# ledSequencer.net
KiCad netlist of a schematic drawn in Altium Designer
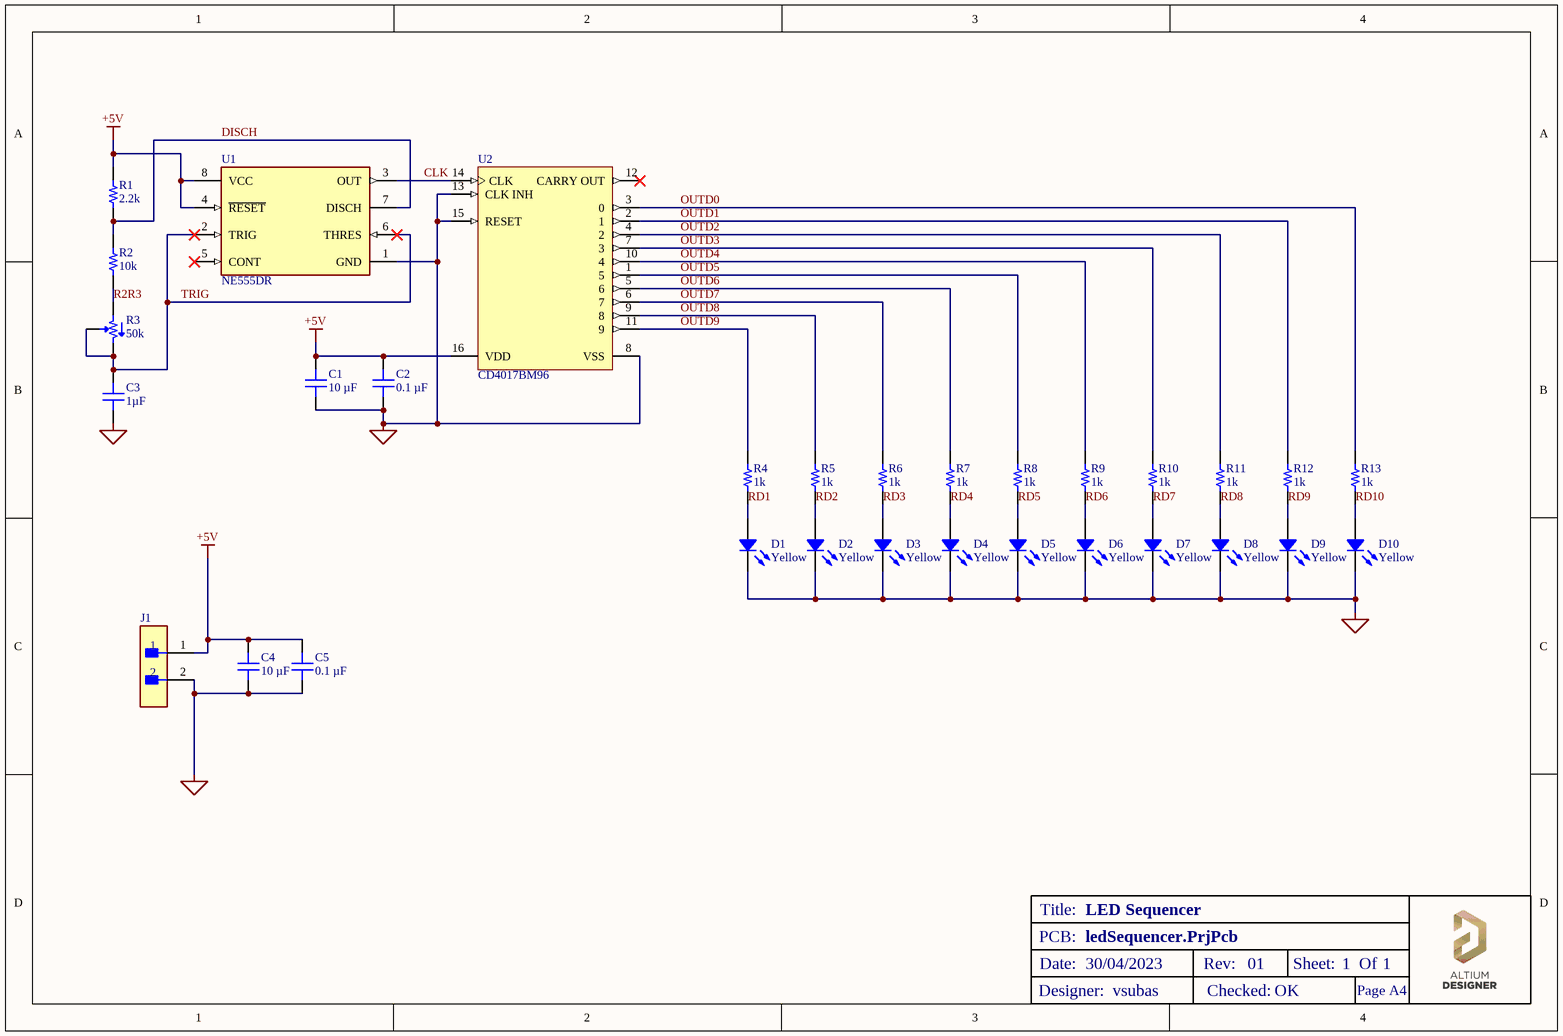
[diagram p0: ledSequencer.SchDoc]

(export (version "E")
  (design (tool "Eeschema 10.0.6"))
  (components
    (comp (ref "C1")
      (value "10 µF")
      (footprint "CAP 0805_2012")
      (description "CAP CER 10UF 25V X5R 0805")
      (fields
        (field (name "PART NUMBER") "C2012X5R1E106K125AB")
        (field (name "MANUFACTURER") "TDK Corporation")
      )
      (libsource (lib "Celestial Altium Library - altium_library") (part "Capacitor"))
    )
    (comp (ref "C2")
      (value "0.1 µF")
      (footprint "CAP 0805_2012")
      (description "CAP CER 0.1UF 50V X7R 0805")
      (fields (field (name "PART NUMBER") "CC0805MRX7R9BB104") (field (name "MANUFACTURER") "Yageo"))
      (libsource (lib "Celestial Altium Library - altium_library") (part "Capacitor"))
    )
    (comp (ref "C3")
      (value "1µF")
      (footprint "CAP 0805_2012")
      (description "CAP CER 1UF 10V X7R 0805")
      (fields (field (name "PART NUMBER") "MM05ZC105KCZ2A") (field (name "MANUFACTURER") "AVX Corporation"))
      (libsource (lib "Celestial Altium Library - altium_library") (part "Capacitor"))
    )
    (comp (ref "C4")
      (value "10 µF")
      (footprint "CAP 0805_2012")
      (description "CAP CER 10UF 25V X5R 0805")
      (fields
        (field (name "PART NUMBER") "C2012X5R1E106K125AB")
        (field (name "MANUFACTURER") "TDK Corporation")
      )
      (libsource (lib "Celestial Altium Library - altium_library") (part "Capacitor"))
    )
    (comp (ref "C5")
      (value "0.1 µF")
      (footprint "CAP 0805_2012")
      (description "CAP CER 0.1UF 50V X7R 0805")
      (fields (field (name "PART NUMBER") "CC0805MRX7R9BB104") (field (name "MANUFACTURER") "Yageo"))
      (libsource (lib "Celestial Altium Library - altium_library") (part "Capacitor"))
    )
    (comp (ref "D1")
      (value "Yellow")
      (footprint "LED 0805_2012 YELLOW")
      (description "LED YELLOW CLEAR 0805 SMD")
      (fields (field (name "PART NUMBER") "5988140107F") (field (name "MANUFACTURER") "Dialight"))
      (libsource (lib "Celestial Altium Library - altium_library") (part "LED"))
    )
    (comp (ref "D2")
      (value "Yellow")
      (footprint "LED 0805_2012 YELLOW")
      (description "LED YELLOW CLEAR 0805 SMD")
      (fields (field (name "PART NUMBER") "5988140107F") (field (name "MANUFACTURER") "Dialight"))
      (libsource (lib "Celestial Altium Library - altium_library") (part "LED"))
    )
    (comp (ref "D3")
      (value "Yellow")
      (footprint "LED 0805_2012 YELLOW")
      (description "LED YELLOW CLEAR 0805 SMD")
      (fields (field (name "PART NUMBER") "5988140107F") (field (name "MANUFACTURER") "Dialight"))
      (libsource (lib "Celestial Altium Library - altium_library") (part "LED"))
    )
    (comp (ref "D4")
      (value "Yellow")
      (footprint "LED 0805_2012 YELLOW")
      (description "LED YELLOW CLEAR 0805 SMD")
      (fields (field (name "PART NUMBER") "5988140107F") (field (name "MANUFACTURER") "Dialight"))
      (libsource (lib "Celestial Altium Library - altium_library") (part "LED"))
    )
    (comp (ref "D5")
      (value "Yellow")
      (footprint "LED 0805_2012 YELLOW")
      (description "LED YELLOW CLEAR 0805 SMD")
      (fields (field (name "PART NUMBER") "5988140107F") (field (name "MANUFACTURER") "Dialight"))
      (libsource (lib "Celestial Altium Library - altium_library") (part "LED"))
    )
    (comp (ref "D6")
      (value "Yellow")
      (footprint "LED 0805_2012 YELLOW")
      (description "LED YELLOW CLEAR 0805 SMD")
      (fields (field (name "PART NUMBER") "5988140107F") (field (name "MANUFACTURER") "Dialight"))
      (libsource (lib "Celestial Altium Library - altium_library") (part "LED"))
    )
    (comp (ref "D7")
      (value "Yellow")
      (footprint "LED 0805_2012 YELLOW")
      (description "LED YELLOW CLEAR 0805 SMD")
      (fields (field (name "PART NUMBER") "5988140107F") (field (name "MANUFACTURER") "Dialight"))
      (libsource (lib "Celestial Altium Library - altium_library") (part "LED"))
    )
    (comp (ref "D8")
      (value "Yellow")
      (footprint "LED 0805_2012 YELLOW")
      (description "LED YELLOW CLEAR 0805 SMD")
      (fields (field (name "PART NUMBER") "5988140107F") (field (name "MANUFACTURER") "Dialight"))
      (libsource (lib "Celestial Altium Library - altium_library") (part "LED"))
    )
    (comp (ref "D9")
      (value "Yellow")
      (footprint "LED 0805_2012 YELLOW")
      (description "LED YELLOW CLEAR 0805 SMD")
      (fields (field (name "PART NUMBER") "5988140107F") (field (name "MANUFACTURER") "Dialight"))
      (libsource (lib "Celestial Altium Library - altium_library") (part "LED"))
    )
    (comp (ref "D10")
      (value "Yellow")
      (footprint "LED 0805_2012 YELLOW")
      (description "LED YELLOW CLEAR 0805 SMD")
      (fields (field (name "PART NUMBER") "5988140107F") (field (name "MANUFACTURER") "Dialight"))
      (libsource (lib "Celestial Altium Library - altium_library") (part "LED"))
    )
    (comp (ref "J1")
      (value "M20-9990245")
      (footprint "FP-M20-9990245-MFG")
      (description "CONN HEADER VERT 2POS 2.54MM")
      (fields (field (name "VOLTAGE") "50V"))
      (libsource (lib "Altium Content Vault") (part "3bc925449376181038e59eaffc5286c"))
    )
    (comp (ref "R1")
      (value "2.2k")
      (footprint "RES 0805_2012")
      (description "RES 2.2K OHM 5% 1/4W 0805")
      (fields (field (name "PART NUMBER") "SR0805JR-7W2K2L") (field (name "MANUFACTURER") "Yageo"))
      (libsource (lib "Celestial Altium Library - altium_library") (part "Resistor"))
    )
    (comp (ref "R2")
      (value "10k")
      (footprint "RES 0805_2012")
      (description "RES 10K OHM 0.1% 1/10W 0805")
      (fields
        (field (name "PART NUMBER") "RNCS0805BKE10K0")
        (field (name "MANUFACTURER") "Stackpole Electronics Inc")
      )
      (libsource (lib "Celestial Altium Library - altium_library") (part "Resistor"))
    )
    (comp (ref "R3")
      (value "50k")
      (footprint "BOURNS TRIMPOT 3386P-1")
      (description "TRIMMER 50K OHM 0.5W PC PIN TOP")
      (fields (field (name "PART NUMBER") "3386P-1-503") (field (name "MANUFACTURER") "Bourns Inc."))
      (libsource (lib "Celestial Altium Library - altium_library") (part "Potentiometer"))
    )
    (comp (ref "R4")
      (value "1k")
      (footprint "RES 0805_2012")
      (description "RES 1K OHM 0.1% 1/10W 0805")
      (fields
        (field (name "PART NUMBER") "RNCS0805BKE1K00")
        (field (name "MANUFACTURER") "Stackpole Electronics Inc")
      )
      (libsource (lib "Celestial Altium Library - altium_library") (part "Resistor"))
    )
    (comp (ref "R5")
      (value "1k")
      (footprint "RES 0805_2012")
      (description "RES 1K OHM 0.1% 1/10W 0805")
      (fields
        (field (name "PART NUMBER") "RNCS0805BKE1K00")
        (field (name "MANUFACTURER") "Stackpole Electronics Inc")
      )
      (libsource (lib "Celestial Altium Library - altium_library") (part "Resistor"))
    )
    (comp (ref "R6")
      (value "1k")
      (footprint "RES 0805_2012")
      (description "RES 1K OHM 0.1% 1/10W 0805")
      (fields
        (field (name "PART NUMBER") "RNCS0805BKE1K00")
        (field (name "MANUFACTURER") "Stackpole Electronics Inc")
      )
      (libsource (lib "Celestial Altium Library - altium_library") (part "Resistor"))
    )
    (comp (ref "R7")
      (value "1k")
      (footprint "RES 0805_2012")
      (description "RES 1K OHM 0.1% 1/10W 0805")
      (fields
        (field (name "PART NUMBER") "RNCS0805BKE1K00")
        (field (name "MANUFACTURER") "Stackpole Electronics Inc")
      )
      (libsource (lib "Celestial Altium Library - altium_library") (part "Resistor"))
    )
    (comp (ref "R8")
      (value "1k")
      (footprint "RES 0805_2012")
      (description "RES 1K OHM 0.1% 1/10W 0805")
      (fields
        (field (name "PART NUMBER") "RNCS0805BKE1K00")
        (field (name "MANUFACTURER") "Stackpole Electronics Inc")
      )
      (libsource (lib "Celestial Altium Library - altium_library") (part "Resistor"))
    )
    (comp (ref "R9")
      (value "1k")
      (footprint "RES 0805_2012")
      (description "RES 1K OHM 0.1% 1/10W 0805")
      (fields
        (field (name "PART NUMBER") "RNCS0805BKE1K00")
        (field (name "MANUFACTURER") "Stackpole Electronics Inc")
      )
      (libsource (lib "Celestial Altium Library - altium_library") (part "Resistor"))
    )
    (comp (ref "R10")
      (value "1k")
      (footprint "RES 0805_2012")
      (description "RES 1K OHM 0.1% 1/10W 0805")
      (fields
        (field (name "PART NUMBER") "RNCS0805BKE1K00")
        (field (name "MANUFACTURER") "Stackpole Electronics Inc")
      )
      (libsource (lib "Celestial Altium Library - altium_library") (part "Resistor"))
    )
    (comp (ref "R11")
      (value "1k")
      (footprint "RES 0805_2012")
      (description "RES 1K OHM 0.1% 1/10W 0805")
      (fields
        (field (name "PART NUMBER") "RNCS0805BKE1K00")
        (field (name "MANUFACTURER") "Stackpole Electronics Inc")
      )
      (libsource (lib "Celestial Altium Library - altium_library") (part "Resistor"))
    )
    (comp (ref "R12")
      (value "1k")
      (footprint "RES 0805_2012")
      (description "RES 1K OHM 0.1% 1/10W 0805")
      (fields
        (field (name "PART NUMBER") "RNCS0805BKE1K00")
        (field (name "MANUFACTURER") "Stackpole Electronics Inc")
      )
      (libsource (lib "Celestial Altium Library - altium_library") (part "Resistor"))
    )
    (comp (ref "R13")
      (value "1k")
      (footprint "RES 0805_2012")
      (description "RES 1K OHM 0.1% 1/10W 0805")
      (fields
        (field (name "PART NUMBER") "RNCS0805BKE1K00")
        (field (name "MANUFACTURER") "Stackpole Electronics Inc")
      )
      (libsource (lib "Celestial Altium Library - altium_library") (part "Resistor"))
    )
    (comp (ref "U1")
      (value "NE555DR")
      (footprint "FP-D0008A-IPC_A")
      (description "IC OSC SGL TIMER 100KHZ 8-SOIC")
      (libsource (lib "Altium Content Vault") (part "a29bba90211dec1890110b94dad7d53"))
    )
    (comp (ref "U2")
      (value "CD4017BM96")
      (footprint "D0016A_L")
      (description "CMOS Decade Counter with 10 Decoded Outputs, D0016A, LARGE T&R")
      (fields
        (field (name "GENERIC PART NUMBER") "CD4017B")
        (field (name "MANUFACTURER") "Texas Instruments")
      )
      (libsource (lib "Altium Content Vault") (part "TI-CD4017B-16"))
    )
  )
  (nets
    (net (code "1") (name "+5V") (class "Default")
      (node (ref "C1") (pin "2") (pinfunction "2_2") (pintype "passive"))
      (node (ref "C2") (pin "2") (pinfunction "2_2") (pintype "passive"))
      (node (ref "C4") (pin "2") (pinfunction "2_2") (pintype "passive"))
      (node (ref "C5") (pin "2") (pinfunction "2_2") (pintype "passive"))
      (node (ref "J1") (pin "1") (pinfunction "1_1") (pintype "passive"))
      (node (ref "R1") (pin "2") (pinfunction "2_2") (pintype "passive"))
      (node (ref "U1") (pin "4") (pinfunction "~{RESET}_4") (pintype "input"))
      (node (ref "U1") (pin "8") (pinfunction "VCC_8") (pintype "power_in"))
      (node (ref "U2") (pin "16") (pinfunction "VDD_16") (pintype "power_in"))
    )
    (net (code "2") (name "/CLK") (class "Default")
      (node (ref "U1") (pin "3") (pinfunction "OUT_3") (pintype "output"))
      (node (ref "U2") (pin "14") (pinfunction "CLK_14") (pintype "input"))
    )
    (net (code "3") (name "/DISCH") (class "Default")
      (node (ref "R1") (pin "1") (pinfunction "1_1") (pintype "passive"))
      (node (ref "R2") (pin "2") (pinfunction "2_2") (pintype "passive"))
      (node (ref "U1") (pin "7") (pinfunction "DISCH_7") (pintype "open_collector"))
    )
    (net (code "4") (name "/OUTD0") (class "Default")
      (node (ref "R13") (pin "1") (pinfunction "1_1") (pintype "passive"))
      (node (ref "U2") (pin "3") (pinfunction "0_3") (pintype "output"))
    )
    (net (code "5") (name "/OUTD1") (class "Default")
      (node (ref "R12") (pin "1") (pinfunction "1_1") (pintype "passive"))
      (node (ref "U2") (pin "2") (pinfunction "1_2") (pintype "output"))
    )
    (net (code "6") (name "/OUTD2") (class "Default")
      (node (ref "R11") (pin "1") (pinfunction "1_1") (pintype "passive"))
      (node (ref "U2") (pin "4") (pinfunction "2_4") (pintype "output"))
    )
    (net (code "7") (name "/OUTD3") (class "Default")
      (node (ref "R10") (pin "1") (pinfunction "1_1") (pintype "passive"))
      (node (ref "U2") (pin "7") (pinfunction "3_7") (pintype "output"))
    )
    (net (code "8") (name "/OUTD4") (class "Default")
      (node (ref "R9") (pin "1") (pinfunction "1_1") (pintype "passive"))
      (node (ref "U2") (pin "10") (pinfunction "4_10") (pintype "output"))
    )
    (net (code "9") (name "/OUTD5") (class "Default")
      (node (ref "R8") (pin "1") (pinfunction "1_1") (pintype "passive"))
      (node (ref "U2") (pin "1") (pinfunction "5_1") (pintype "output"))
    )
    (net (code "10") (name "/OUTD6") (class "Default")
      (node (ref "R7") (pin "1") (pinfunction "1_1") (pintype "passive"))
      (node (ref "U2") (pin "5") (pinfunction "6_5") (pintype "output"))
    )
    (net (code "11") (name "/OUTD7") (class "Default")
      (node (ref "R6") (pin "1") (pinfunction "1_1") (pintype "passive"))
      (node (ref "U2") (pin "6") (pinfunction "7_6") (pintype "output"))
    )
    (net (code "12") (name "/OUTD8") (class "Default")
      (node (ref "R5") (pin "1") (pinfunction "1_1") (pintype "passive"))
      (node (ref "U2") (pin "9") (pinfunction "8_9") (pintype "output"))
    )
    (net (code "13") (name "/OUTD9") (class "Default")
      (node (ref "R4") (pin "1") (pinfunction "1_1") (pintype "passive"))
      (node (ref "U2") (pin "11") (pinfunction "9_11") (pintype "output"))
    )
    (net (code "14") (name "/R2R3") (class "Default")
      (node (ref "R2") (pin "1") (pinfunction "1_1") (pintype "passive"))
      (node (ref "R3") (pin "1") (pinfunction "1_1") (pintype "passive"))
    )
    (net (code "15") (name "/RD1") (class "Default")
      (node (ref "D1") (pin "1") (pinfunction "1_1") (pintype "passive"))
      (node (ref "R4") (pin "2") (pinfunction "2_2") (pintype "passive"))
    )
    (net (code "16") (name "/RD2") (class "Default")
      (node (ref "D2") (pin "1") (pinfunction "1_1") (pintype "passive"))
      (node (ref "R5") (pin "2") (pinfunction "2_2") (pintype "passive"))
    )
    (net (code "17") (name "/RD3") (class "Default")
      (node (ref "D3") (pin "1") (pinfunction "1_1") (pintype "passive"))
      (node (ref "R6") (pin "2") (pinfunction "2_2") (pintype "passive"))
    )
    (net (code "18") (name "/RD4") (class "Default")
      (node (ref "D4") (pin "1") (pinfunction "1_1") (pintype "passive"))
      (node (ref "R7") (pin "2") (pinfunction "2_2") (pintype "passive"))
    )
    (net (code "19") (name "/RD5") (class "Default")
      (node (ref "D5") (pin "1") (pinfunction "1_1") (pintype "passive"))
      (node (ref "R8") (pin "2") (pinfunction "2_2") (pintype "passive"))
    )
    (net (code "20") (name "/RD6") (class "Default")
      (node (ref "D6") (pin "1") (pinfunction "1_1") (pintype "passive"))
      (node (ref "R9") (pin "2") (pinfunction "2_2") (pintype "passive"))
    )
    (net (code "21") (name "/RD7") (class "Default")
      (node (ref "D7") (pin "1") (pinfunction "1_1") (pintype "passive"))
      (node (ref "R10") (pin "2") (pinfunction "2_2") (pintype "passive"))
    )
    (net (code "22") (name "/RD8") (class "Default")
      (node (ref "D8") (pin "1") (pinfunction "1_1") (pintype "passive"))
      (node (ref "R11") (pin "2") (pinfunction "2_2") (pintype "passive"))
    )
    (net (code "23") (name "/RD9") (class "Default")
      (node (ref "D9") (pin "1") (pinfunction "1_1") (pintype "passive"))
      (node (ref "R12") (pin "2") (pinfunction "2_2") (pintype "passive"))
    )
    (net (code "24") (name "/RD10") (class "Default")
      (node (ref "D10") (pin "1") (pinfunction "1_1") (pintype "passive"))
      (node (ref "R13") (pin "2") (pinfunction "2_2") (pintype "passive"))
    )
    (net (code "25") (name "/TRIG") (class "Default")
      (node (ref "C3") (pin "2") (pinfunction "2_2") (pintype "passive"))
      (node (ref "R3") (pin "2") (pinfunction "2_2") (pintype "passive"))
      (node (ref "R3") (pin "3") (pinfunction "3_3") (pintype "passive"))
      (node (ref "U1") (pin "2") (pinfunction "TRIG_2") (pintype "input"))
      (node (ref "U1") (pin "6") (pinfunction "THRES_6") (pintype "input"))
    )
    (net (code "26") (name "GND") (class "Default")
      (node (ref "C1") (pin "1") (pinfunction "1_1") (pintype "passive"))
      (node (ref "C2") (pin "1") (pinfunction "1_1") (pintype "passive"))
      (node (ref "C3") (pin "1") (pinfunction "1_1") (pintype "passive"))
      (node (ref "C4") (pin "1") (pinfunction "1_1") (pintype "passive"))
      (node (ref "C5") (pin "1") (pinfunction "1_1") (pintype "passive"))
      (node (ref "D1") (pin "2") (pinfunction "2_2") (pintype "passive"))
      (node (ref "D10") (pin "2") (pinfunction "2_2") (pintype "passive"))
      (node (ref "D2") (pin "2") (pinfunction "2_2") (pintype "passive"))
      (node (ref "D3") (pin "2") (pinfunction "2_2") (pintype "passive"))
      (node (ref "D4") (pin "2") (pinfunction "2_2") (pintype "passive"))
      (node (ref "D5") (pin "2") (pinfunction "2_2") (pintype "passive"))
      (node (ref "D6") (pin "2") (pinfunction "2_2") (pintype "passive"))
      (node (ref "D7") (pin "2") (pinfunction "2_2") (pintype "passive"))
      (node (ref "D8") (pin "2") (pinfunction "2_2") (pintype "passive"))
      (node (ref "D9") (pin "2") (pinfunction "2_2") (pintype "passive"))
      (node (ref "J1") (pin "2") (pinfunction "2_2") (pintype "passive"))
      (node (ref "U1") (pin "1") (pinfunction "GND_1") (pintype "power_in"))
      (node (ref "U2") (pin "13") (pinfunction "CLK_INH_13") (pintype "input"))
      (node (ref "U2") (pin "15") (pinfunction "RESET_15") (pintype "input"))
      (node (ref "U2") (pin "8") (pinfunction "VSS_8") (pintype "power_in"))
    )
    (net (code "27") (name "unconnected-(U1-CONT-Pad5)") (class "Default")
      (node (ref "U1") (pin "5") (pinfunction "CONT_5") (pintype "input+no_connect"))
    )
    (net (code "28") (name "unconnected-(U2-CARRY_OUT-Pad12)") (class "Default")
      (node (ref "U2") (pin "12") (pinfunction "CARRY_OUT_12") (pintype "output+no_connect"))
    )
  )
)
